# usb-to-uart.net
KiCad netlist of a schematic drawn in Altium Designer
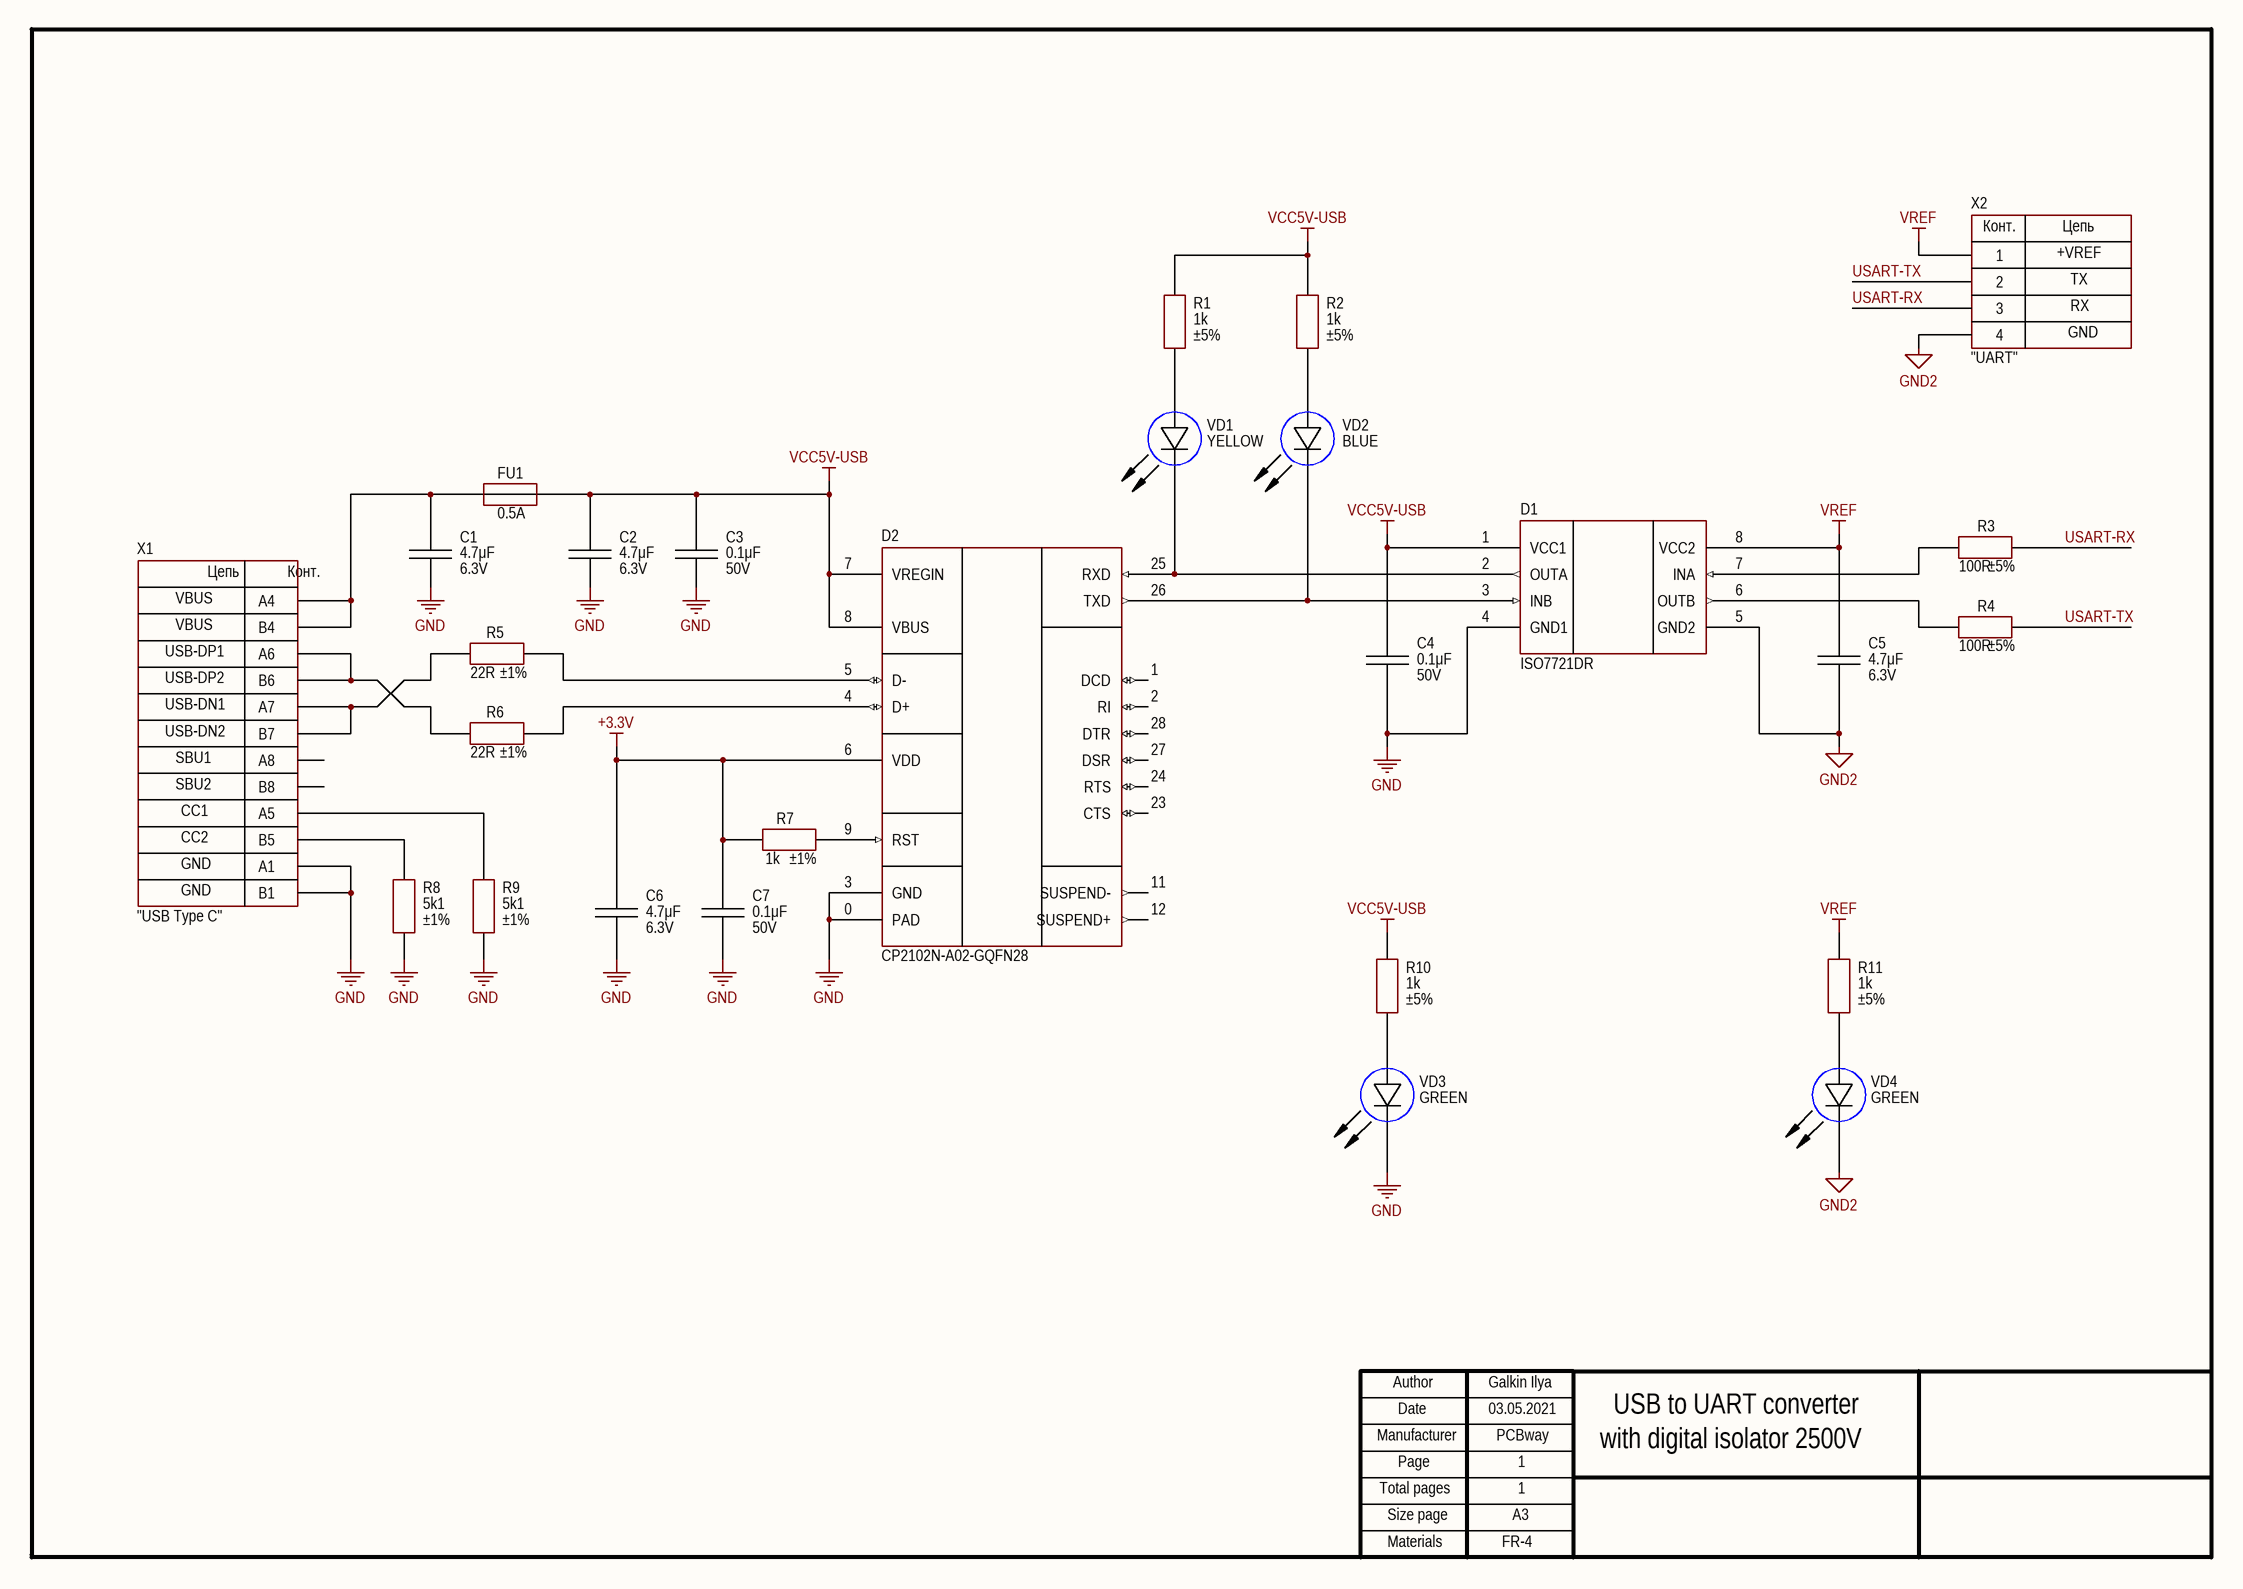
[diagram p0: usb-to-uart.SchDoc]

(export (version "E")
  (design (tool "Eeschema 10.0.6"))
  (components
    (comp (ref "C1")
      (value "4.7μF")
      (footprint "CAP: 0603")
      (fields
        (field (name "MANUFACTURER") "Samsung")
        (field (name "PARTNUMBER") "CL10B475KQ8NQNC")
        (field (name "VALUEMANUFACTURERPARTNUMBER") "Ceramic capacitor, 4.7μF, X7R, ±10%, 6.3V, 0603, -55...+125°C")
        (field (name "VOLTAGE") "6.3V")
      )
      (libsource (lib "capacitor") (part "Ceramic_0603"))
    )
    (comp (ref "C2")
      (value "4.7μF")
      (footprint "CAP: 0603")
      (fields
        (field (name "MANUFACTURER") "Samsung")
        (field (name "PARTNUMBER") "CL10B475KQ8NQNC")
        (field (name "VALUEMANUFACTURERPARTNUMBER") "Ceramic capacitor, 4.7μF, X7R, ±10%, 6.3V, 0603, -55...+125°C")
        (field (name "VOLTAGE") "6.3V")
      )
      (libsource (lib "capacitor") (part "Ceramic_0603"))
    )
    (comp (ref "C3")
      (value "0.1μF")
      (footprint "CAP: 0603")
      (fields
        (field (name "MANUFACTURER") "Samsung")
        (field (name "PARTNUMBER") "CL10B104KB8NNNL")
        (field (name "VALUEMANUFACTURERPARTNUMBER") "Ceramic capacitor, 0.1μF, X7R, ±10%, 50V, 0603, -55...+125°C")
        (field (name "VOLTAGE") "50V")
      )
      (libsource (lib "capacitor") (part "Ceramic_0603"))
    )
    (comp (ref "C4")
      (value "0.1μF")
      (footprint "CAP: 0603")
      (fields
        (field (name "MANUFACTURER") "Samsung")
        (field (name "PARTNUMBER") "CL10B104KB8NNNL")
        (field (name "VALUEMANUFACTURERPARTNUMBER") "Ceramic capacitor, 0.1μF, X7R, ±10%, 50V, 0603, -55...+125°C")
        (field (name "VOLTAGE") "50V")
      )
      (libsource (lib "capacitor") (part "Ceramic_0603"))
    )
    (comp (ref "C5")
      (value "4.7μF")
      (footprint "CAP: 0603")
      (fields
        (field (name "MANUFACTURER") "Samsung")
        (field (name "PARTNUMBER") "CL10B475KQ8NQNC")
        (field (name "VALUEMANUFACTURERPARTNUMBER") "Ceramic capacitor, 4.7μF, X7R, ±10%, 6.3V, 0603, -55...+125°C")
        (field (name "VOLTAGE") "6.3V")
      )
      (libsource (lib "capacitor") (part "Ceramic_0603"))
    )
    (comp (ref "C6")
      (value "4.7μF")
      (footprint "CAP: 0603")
      (fields
        (field (name "MANUFACTURER") "Samsung")
        (field (name "PARTNUMBER") "CL10B475KQ8NQNC")
        (field (name "VALUEMANUFACTURERPARTNUMBER") "Ceramic capacitor, 4.7μF, X7R, ±10%, 6.3V, 0603, -55...+125°C")
        (field (name "VOLTAGE") "6.3V")
      )
      (libsource (lib "capacitor") (part "Ceramic_0603"))
    )
    (comp (ref "C7")
      (value "0.1μF")
      (footprint "CAP: 0603")
      (fields
        (field (name "MANUFACTURER") "Samsung")
        (field (name "PARTNUMBER") "CL10B104KB8NNNL")
        (field (name "VALUEMANUFACTURERPARTNUMBER") "Ceramic capacitor, 0.1μF, X7R, ±10%, 50V, 0603, -55...+125°C")
        (field (name "VOLTAGE") "50V")
      )
      (libsource (lib "capacitor") (part "Ceramic_0603"))
    )
    (comp (ref "D1")
      (value "~")
      (footprint "8-SOIC")
      (description "Digital isolator 1/1")
      (fields
        (field (name "MANUFACTURER") "Texas Instruments")
        (field (name "VALUEMANUFACTURERPARTNUMBER") "IC digital isolator, 100Mbps, 3000Vrms, 2.25...5.5V, -55...+125°C, 8-SOIC")
        (field (name "PARTNUMBER") "ISO7721DR")
      )
      (libsource (lib "ic-interface") (part "ISO7721DR"))
    )
    (comp (ref "D2")
      (value "~")
      (footprint "28-QFN (5x5)")
      (description "USB-to-UART")
      (fields
        (field (name "MANUFACTURER") "Silicon Labs")
        (field (name "VALUEMANUFACTURERPARTNUMBER") "IC usb-to-uart bridge, USB2.0, 3...3.6V, -40...+85°C, 28-VFQFN")
        (field (name "PARTNUMBER") "CP2102N-A02-GQFN28")
      )
      (libsource (lib "ic-interface") (part "CP2102N"))
    )
    (comp (ref "FU1")
      (value "~")
      (footprint "FUSE: 0603")
      (fields
        (field (name "MANUFACTURER") "Eaton")
        (field (name "VALUEMANUFACTURERPARTNUMBER") "Electromechanics relay, 63VDC, 0.5A, case 0603, ")
        (field (name "PARTNUMBER") "TR-0603HV500-R")
        (field (name "MAXCURRENT") "0.5A")
      )
      (libsource (lib "electromechanics") (part "Fuse"))
    )
    (comp (ref "R1")
      (value "1k")
      (footprint "RES: 0603")
      (fields
        (field (name "MANUFACTURER") "Yageo")
        (field (name "PARTNUMBER") "RC0603JR-071KL")
        (field (name "VALUEMANUFACTURERPARTNUMBER") "Resistor film, 1k, ±5%, 0603, 0.1W, -55...+125°C")
        (field (name "TOLERANCE") "±5%")
      )
      (libsource (lib "") (part "Resistor_0603_1"))
    )
    (comp (ref "R2")
      (value "1k")
      (footprint "RES: 0603")
      (fields
        (field (name "MANUFACTURER") "Yageo")
        (field (name "PARTNUMBER") "RC0603JR-071KL")
        (field (name "VALUEMANUFACTURERPARTNUMBER") "Resistor film, 1k, ±5%, 0603, 0.1W, -55...+125°C")
        (field (name "TOLERANCE") "±5%")
      )
      (libsource (lib "") (part "Resistor_0603_1"))
    )
    (comp (ref "R3")
      (value "100R")
      (footprint "RES: 0603")
      (fields
        (field (name "MANUFACTURER") "Yageo")
        (field (name "PARTNUMBER") "RC0603JR-07100RL")
        (field (name "VALUEMANUFACTURERPARTNUMBER") "Resistor film, 100R, ±5%, 0603, 0.1W, -55...+125°C")
        (field (name "TOLERANCE") "±5%")
      )
      (libsource (lib "") (part "Resistor_0603_2"))
    )
    (comp (ref "R4")
      (value "100R")
      (footprint "RES: 0603")
      (fields
        (field (name "MANUFACTURER") "Yageo")
        (field (name "PARTNUMBER") "RC0603JR-07100RL")
        (field (name "VALUEMANUFACTURERPARTNUMBER") "Resistor film, 100R, ±5%, 0603, 0.1W, -55...+125°C")
        (field (name "TOLERANCE") "±5%")
      )
      (libsource (lib "") (part "Resistor_0603_2"))
    )
    (comp (ref "R5")
      (value "22R")
      (footprint "RES: 0603")
      (fields
        (field (name "MANUFACTURER") "Yageo")
        (field (name "PARTNUMBER") "RC0603FR-0722RL")
        (field (name "VALUEMANUFACTURERPARTNUMBER") "Resistor film, 22R, ±1%, 0603, 0.1W, -55...+125°C")
        (field (name "TOLERANCE") "±1%")
      )
      (libsource (lib "Resistor") (part "Resistor_0603"))
    )
    (comp (ref "R6")
      (value "22R")
      (footprint "RES: 0603")
      (fields
        (field (name "MANUFACTURER") "Yageo")
        (field (name "PARTNUMBER") "RC0603FR-0722RL")
        (field (name "VALUEMANUFACTURERPARTNUMBER") "Resistor film, 22R, ±1%, 0603, 0.1W, -55...+125°C")
        (field (name "TOLERANCE") "±1%")
      )
      (libsource (lib "Resistor") (part "Resistor_0603"))
    )
    (comp (ref "R7")
      (value "1k")
      (footprint "RES: 0603")
      (fields
        (field (name "MANUFACTURER") "Yageo")
        (field (name "PARTNUMBER") "RC0603FR-071KL")
        (field (name "VALUEMANUFACTURERPARTNUMBER") "Resistor film, 1k, ±1%, 0603, 0.1W, -55...+125°C")
        (field (name "TOLERANCE") "±1%")
      )
      (libsource (lib "") (part "Resistor_0603_1"))
    )
    (comp (ref "R8")
      (value "5k1")
      (footprint "RES: 0603")
      (fields
        (field (name "MANUFACTURER") "Yageo")
        (field (name "PARTNUMBER") "RC0603FR-075K1L")
        (field (name "VALUEMANUFACTURERPARTNUMBER") "Resistor film, 5k1, ±1%, 0603, 0.1W, -55...+125°C")
        (field (name "TOLERANCE") "±1%")
      )
      (libsource (lib "resistor") (part "Resistor_0603"))
    )
    (comp (ref "R9")
      (value "5k1")
      (footprint "RES: 0603")
      (fields
        (field (name "MANUFACTURER") "Yageo")
        (field (name "PARTNUMBER") "RC0603FR-075K1L")
        (field (name "VALUEMANUFACTURERPARTNUMBER") "Resistor film, 5k1, ±1%, 0603, 0.1W, -55...+125°C")
        (field (name "TOLERANCE") "±1%")
      )
      (libsource (lib "resistor") (part "Resistor_0603"))
    )
    (comp (ref "R10")
      (value "1k")
      (footprint "RES: 0603")
      (fields
        (field (name "MANUFACTURER") "Yageo")
        (field (name "PARTNUMBER") "RC0603JR-071KL")
        (field (name "VALUEMANUFACTURERPARTNUMBER") "Resistor film, 1k, ±5%, 0603, 0.1W, -55...+125°C")
        (field (name "TOLERANCE") "±5%")
      )
      (libsource (lib "") (part "Resistor_0603_1"))
    )
    (comp (ref "R11")
      (value "1k")
      (footprint "RES: 0603")
      (fields
        (field (name "MANUFACTURER") "Yageo")
        (field (name "PARTNUMBER") "RC0603JR-071KL")
        (field (name "VALUEMANUFACTURERPARTNUMBER") "Resistor film, 1k, ±5%, 0603, 0.1W, -55...+125°C")
        (field (name "TOLERANCE") "±5%")
      )
      (libsource (lib "") (part "Resistor_0603_1"))
    )
    (comp (ref "VD1")
      (value "~")
      (footprint "LED: 0603Y")
      (fields
        (field (name "MANUFACTURER") "Wurth")
        (field (name "VALUEMANUFACTURERPARTNUMBER") "LED, 20mA, 2V, 0603, -55...+150°C")
        (field (name "PARTNUMBER") "150060YS75000")
        (field (name "COLOR") "YELLOW")
      )
      (libsource (lib "Diode") (part "LED_single"))
    )
    (comp (ref "VD2")
      (value "~")
      (footprint "LED: 0603B")
      (fields
        (field (name "MANUFACTURER") "Wurth")
        (field (name "VALUEMANUFACTURERPARTNUMBER") "LED, 20mA, 3.2V, 0603, -55...+150°C")
        (field (name "PARTNUMBER") "150060BS75000")
        (field (name "COLOR") "BLUE")
      )
      (libsource (lib "Diode") (part "LED_single"))
    )
    (comp (ref "VD3")
      (value "~")
      (footprint "LED: 0603G")
      (fields
        (field (name "MANUFACTURER") "Wurth")
        (field (name "VALUEMANUFACTURERPARTNUMBER") "LED, 20mA, 2V, 0603, -55...+150°C")
        (field (name "PARTNUMBER") "150060VS75000")
        (field (name "COLOR") "GREEN")
      )
      (libsource (lib "Diode") (part "LED_single"))
    )
    (comp (ref "VD4")
      (value "~")
      (footprint "LED: 0603G")
      (fields
        (field (name "MANUFACTURER") "Wurth")
        (field (name "VALUEMANUFACTURERPARTNUMBER") "LED, 20mA, 2V, 0603, -55...+150°C")
        (field (name "PARTNUMBER") "150060VS75000")
        (field (name "COLOR") "GREEN")
      )
      (libsource (lib "Diode") (part "LED_single"))
    )
    (comp (ref "X1")
      (value "~")
      (footprint "CON: TYPE-C-31-M-12")
      (fields
        (field (name "MANUFACTURER") "Korean Hroparts")
        (field (name "VALUEMANUFACTURERPARTNUMBER") "USB Type C, 3A")
        (field (name "PARTNUMBER") "TYPE-C-31-M-12")
        (field (name "COMMENTTEXT") "\"USB Type C\"")
      )
      (libsource (lib "connector") (part "Connector_USB_Type_C"))
    )
    (comp (ref "X2")
      (value "~")
      (footprint "CON: PLS-4R")
      (fields
        (field (name "MANUFACTURER") "Connfly")
        (field (name "VALUEMANUFACTURERPARTNUMBER") "Connector, 4pin, 2.54mm, 500VAC, 3A")
        (field (name "PARTNUMBER") "PLS-4R")
        (field (name "COMMENTTEXT") "\"UART\"")
      )
      (libsource (lib "connector") (part "PLS-4"))
    )
  )
  (nets
    (net (code "1") (name "+3.3V") (class "Default")
      (node (ref "C6") (pin "2") (pinfunction "2_2") (pintype "passive"))
      (node (ref "C7") (pin "2") (pinfunction "2_2") (pintype "passive"))
      (node (ref "D2") (pin "6") (pinfunction "VDD_6") (pintype "passive"))
      (node (ref "R7") (pin "1") (pinfunction "1_1") (pintype "passive"))
    )
    (net (code "2") (name "/USART-RX") (class "Default")
      (node (ref "R3") (pin "2") (pinfunction "2_2") (pintype "passive"))
      (node (ref "X2") (pin "3") (pinfunction "3_3") (pintype "power_in"))
    )
    (net (code "3") (name "/USART-TX") (class "Default")
      (node (ref "R4") (pin "2") (pinfunction "2_2") (pintype "passive"))
      (node (ref "X2") (pin "2") (pinfunction "2_2") (pintype "passive"))
    )
    (net (code "4") (name "GND") (class "Default")
      (node (ref "C1") (pin "1") (pinfunction "1_1") (pintype "passive"))
      (node (ref "C2") (pin "1") (pinfunction "1_1") (pintype "passive"))
      (node (ref "C3") (pin "1") (pinfunction "1_1") (pintype "passive"))
      (node (ref "C4") (pin "1") (pinfunction "1_1") (pintype "passive"))
      (node (ref "C6") (pin "1") (pinfunction "1_1") (pintype "passive"))
      (node (ref "C7") (pin "1") (pinfunction "1_1") (pintype "passive"))
      (node (ref "D1") (pin "4") (pinfunction "GND1_4") (pintype "passive"))
      (node (ref "D2") (pin "0") (pinfunction "PAD_0") (pintype "passive"))
      (node (ref "D2") (pin "3") (pinfunction "GND_3") (pintype "passive"))
      (node (ref "R8") (pin "1") (pinfunction "1_1") (pintype "passive"))
      (node (ref "R9") (pin "1") (pinfunction "1_1") (pintype "passive"))
      (node (ref "VD3") (pin "2") (pinfunction "C_2") (pintype "passive"))
      (node (ref "X1") (pin "A1") (pinfunction "A1_A1") (pintype "power_in"))
      (node (ref "X1") (pin "B1") (pinfunction "B1_B1") (pintype "power_in"))
    )
    (net (code "5") (name "GND2") (class "Default")
      (node (ref "C5") (pin "1") (pinfunction "1_1") (pintype "passive"))
      (node (ref "D1") (pin "5") (pinfunction "GND2_5") (pintype "passive"))
      (node (ref "VD4") (pin "2") (pinfunction "C_2") (pintype "passive"))
      (node (ref "X2") (pin "4") (pinfunction "4_4") (pintype "power_in"))
    )
    (net (code "6") (name "Net-(C1-Pad2)") (class "Default")
      (node (ref "C1") (pin "2") (pinfunction "2_2") (pintype "passive"))
      (node (ref "FU1") (pin "1") (pinfunction "1_1") (pintype "passive"))
      (node (ref "X1") (pin "A4") (pinfunction "A4_A4") (pintype "passive"))
      (node (ref "X1") (pin "B4") (pinfunction "B4_B4") (pintype "passive"))
    )
    (net (code "7") (name "Net-(D1-INA)") (class "Default")
      (node (ref "D1") (pin "7") (pinfunction "INA_7") (pintype "input"))
      (node (ref "R3") (pin "1") (pinfunction "1_1") (pintype "passive"))
    )
    (net (code "8") (name "Net-(D1-INB)") (class "Default")
      (node (ref "D1") (pin "3") (pinfunction "INB_3") (pintype "input"))
      (node (ref "D2") (pin "26") (pinfunction "TXD_26") (pintype "output"))
      (node (ref "VD2") (pin "2") (pinfunction "C_2") (pintype "passive"))
    )
    (net (code "9") (name "Net-(D1-OUTA)") (class "Default")
      (node (ref "D1") (pin "2") (pinfunction "OUTA_2") (pintype "output"))
      (node (ref "D2") (pin "25") (pinfunction "RXD_25") (pintype "input"))
      (node (ref "VD1") (pin "2") (pinfunction "C_2") (pintype "passive"))
    )
    (net (code "10") (name "Net-(D1-OUTB)") (class "Default")
      (node (ref "D1") (pin "6") (pinfunction "OUTB_6") (pintype "output"))
      (node (ref "R4") (pin "1") (pinfunction "1_1") (pintype "passive"))
    )
    (net (code "11") (name "Net-(D2-D+)") (class "Default")
      (node (ref "D2") (pin "4") (pinfunction "D+_4") (pintype "bidirectional"))
      (node (ref "R6") (pin "1") (pinfunction "1_1") (pintype "passive"))
    )
    (net (code "12") (name "Net-(D2-D-)") (class "Default")
      (node (ref "D2") (pin "5") (pinfunction "D-_5") (pintype "bidirectional"))
      (node (ref "R5") (pin "1") (pinfunction "1_1") (pintype "passive"))
    )
    (net (code "13") (name "Net-(D2-RST)") (class "Default")
      (node (ref "D2") (pin "9") (pinfunction "RST_9") (pintype "input"))
      (node (ref "R7") (pin "2") (pinfunction "2_2") (pintype "passive"))
    )
    (net (code "14") (name "Net-(R5-Pad2)") (class "Default")
      (node (ref "R5") (pin "2") (pinfunction "2_2") (pintype "passive"))
      (node (ref "X1") (pin "A7") (pinfunction "A7_A7") (pintype "power_in"))
      (node (ref "X1") (pin "B7") (pinfunction "B7_B7") (pintype "power_in"))
    )
    (net (code "15") (name "Net-(R6-Pad2)") (class "Default")
      (node (ref "R6") (pin "2") (pinfunction "2_2") (pintype "passive"))
      (node (ref "X1") (pin "A6") (pinfunction "A6_A6") (pintype "power_in"))
      (node (ref "X1") (pin "B6") (pinfunction "B6_B6") (pintype "power_in"))
    )
    (net (code "16") (name "Net-(R8-Pad2)") (class "Default")
      (node (ref "R8") (pin "2") (pinfunction "2_2") (pintype "passive"))
      (node (ref "X1") (pin "B5") (pinfunction "B5_B5") (pintype "power_in"))
    )
    (net (code "17") (name "Net-(R9-Pad2)") (class "Default")
      (node (ref "R9") (pin "2") (pinfunction "2_2") (pintype "passive"))
      (node (ref "X1") (pin "A5") (pinfunction "A5_A5") (pintype "power_in"))
    )
    (net (code "18") (name "Net-(VD1-A)") (class "Default")
      (node (ref "R1") (pin "1") (pinfunction "1_1") (pintype "passive"))
      (node (ref "VD1") (pin "1") (pinfunction "A_1") (pintype "passive"))
    )
    (net (code "19") (name "Net-(VD2-A)") (class "Default")
      (node (ref "R2") (pin "1") (pinfunction "1_1") (pintype "passive"))
      (node (ref "VD2") (pin "1") (pinfunction "A_1") (pintype "passive"))
    )
    (net (code "20") (name "Net-(VD3-A)") (class "Default")
      (node (ref "R10") (pin "1") (pinfunction "1_1") (pintype "passive"))
      (node (ref "VD3") (pin "1") (pinfunction "A_1") (pintype "passive"))
    )
    (net (code "21") (name "Net-(VD4-A)") (class "Default")
      (node (ref "R11") (pin "1") (pinfunction "1_1") (pintype "passive"))
      (node (ref "VD4") (pin "1") (pinfunction "A_1") (pintype "passive"))
    )
    (net (code "22") (name "VCC5V-USB") (class "Default")
      (node (ref "C2") (pin "2") (pinfunction "2_2") (pintype "passive"))
      (node (ref "C3") (pin "2") (pinfunction "2_2") (pintype "passive"))
      (node (ref "C4") (pin "2") (pinfunction "2_2") (pintype "passive"))
      (node (ref "D1") (pin "1") (pinfunction "VCC1_1") (pintype "passive"))
      (node (ref "D2") (pin "7") (pinfunction "VREGIN_7") (pintype "passive"))
      (node (ref "D2") (pin "8") (pinfunction "VBUS_8") (pintype "passive"))
      (node (ref "FU1") (pin "2") (pinfunction "2_2") (pintype "passive"))
      (node (ref "R1") (pin "2") (pinfunction "2_2") (pintype "passive"))
      (node (ref "R10") (pin "2") (pinfunction "2_2") (pintype "passive"))
      (node (ref "R2") (pin "2") (pinfunction "2_2") (pintype "passive"))
    )
    (net (code "23") (name "VREF") (class "Default")
      (node (ref "C5") (pin "2") (pinfunction "2_2") (pintype "passive"))
      (node (ref "D1") (pin "8") (pinfunction "VCC2_8") (pintype "passive"))
      (node (ref "R11") (pin "2") (pinfunction "2_2") (pintype "passive"))
      (node (ref "X2") (pin "1") (pinfunction "1_1") (pintype "passive"))
    )
    (net (code "24") (name "unconnected-(D2-CTS-Pad23)") (class "Default")
      (node (ref "D2") (pin "23") (pinfunction "CTS_23") (pintype "bidirectional"))
    )
    (net (code "25") (name "unconnected-(D2-DCD-Pad1)") (class "Default")
      (node (ref "D2") (pin "1") (pinfunction "DCD_1") (pintype "bidirectional"))
    )
    (net (code "26") (name "unconnected-(D2-DSR-Pad27)") (class "Default")
      (node (ref "D2") (pin "27") (pinfunction "DSR_27") (pintype "bidirectional"))
    )
    (net (code "27") (name "unconnected-(D2-DTR-Pad28)") (class "Default")
      (node (ref "D2") (pin "28") (pinfunction "DTR_28") (pintype "bidirectional"))
    )
    (net (code "28") (name "unconnected-(D2-RI-Pad2)") (class "Default")
      (node (ref "D2") (pin "2") (pinfunction "RI_2") (pintype "bidirectional"))
    )
    (net (code "29") (name "unconnected-(D2-RTS-Pad24)") (class "Default")
      (node (ref "D2") (pin "24") (pinfunction "RTS_24") (pintype "bidirectional"))
    )
    (net (code "30") (name "unconnected-(D2-SUSPEND+-Pad12)") (class "Default")
      (node (ref "D2") (pin "12") (pinfunction "SUSPEND+_12") (pintype "output"))
    )
    (net (code "31") (name "unconnected-(D2-SUSPEND--Pad11)") (class "Default")
      (node (ref "D2") (pin "11") (pinfunction "SUSPEND-_11") (pintype "output"))
    )
    (net (code "32") (name "unconnected-(X1-PadA8)") (class "Default")
      (node (ref "X1") (pin "A8") (pinfunction "A8_A8") (pintype "power_in"))
    )
    (net (code "33") (name "unconnected-(X1-PadB8)") (class "Default")
      (node (ref "X1") (pin "B8") (pinfunction "B8_B8") (pintype "power_in"))
    )
  )
)
